# LED_KEY.net
KiCad netlist of a schematic drawn in Altium Designer
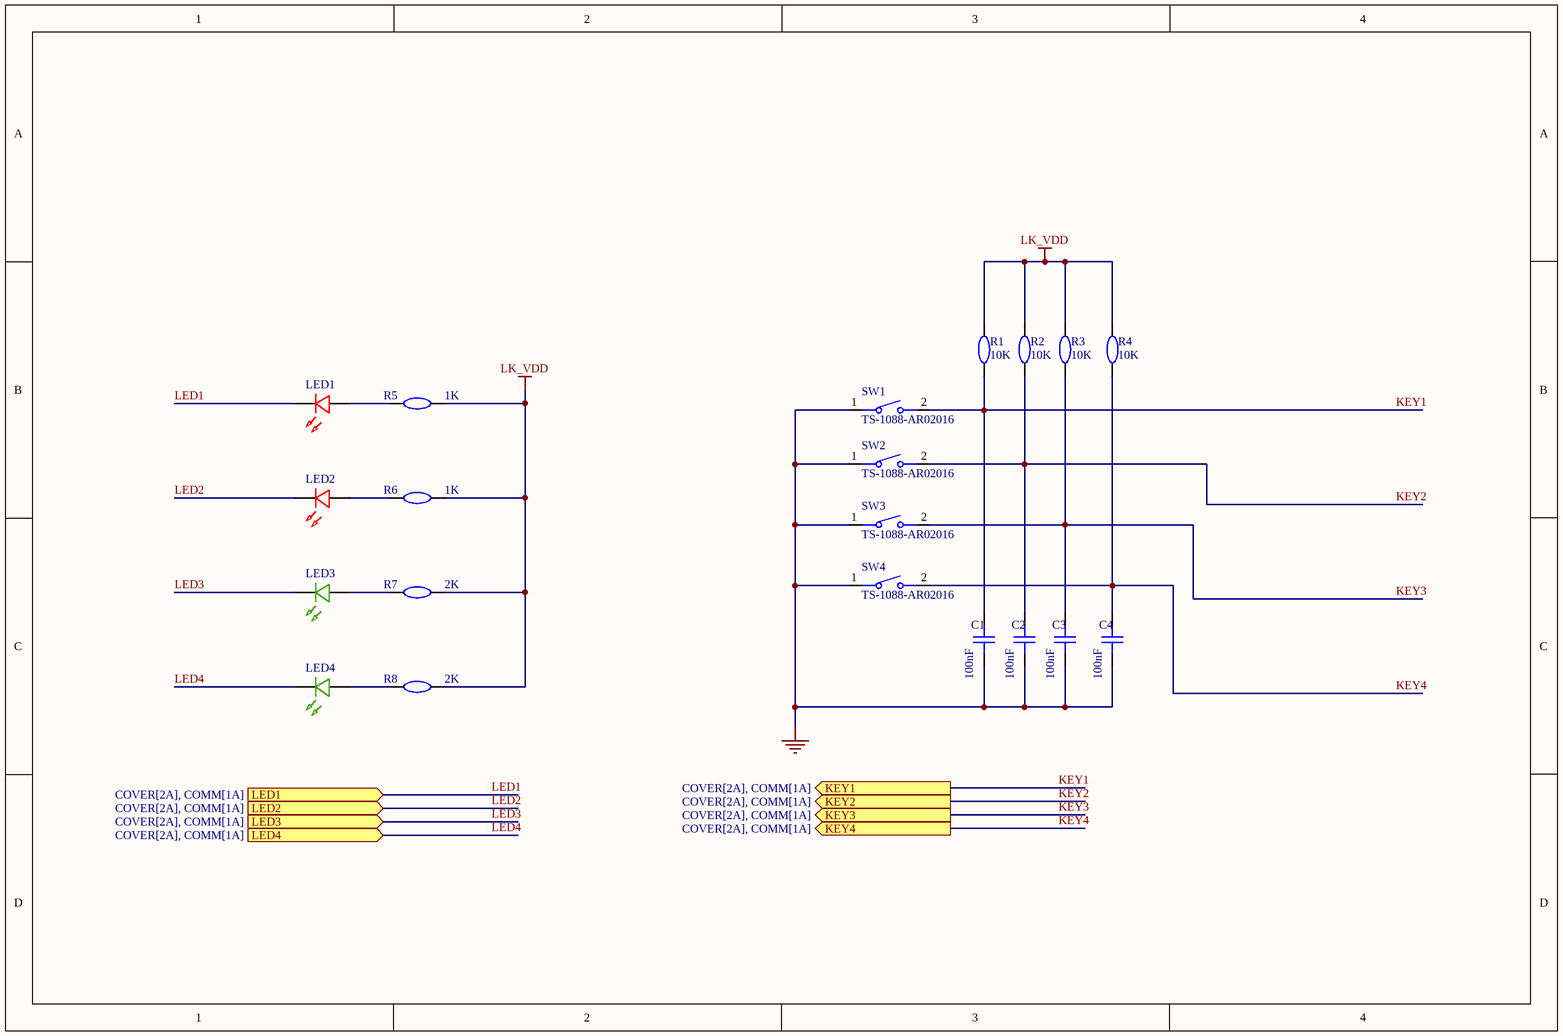
[diagram p0: LED+KEY.SchDoc]

(export (version "E")
  (design (tool "Eeschema 10.0.6"))
  (components
    (comp (ref "C1")
      (value "100nF")
      (footprint "C0402")
      (fields (field (name "NAME") "100nF"))
      (libsource (lib "my_library") (part "CAP_0402"))
    )
    (comp (ref "C2")
      (value "100nF")
      (footprint "C0402")
      (fields (field (name "NAME") "100nF"))
      (libsource (lib "my_library") (part "CAP_0402"))
    )
    (comp (ref "C3")
      (value "100nF")
      (footprint "C0402")
      (fields (field (name "NAME") "100nF"))
      (libsource (lib "my_library") (part "CAP_0402"))
    )
    (comp (ref "C4")
      (value "100nF")
      (footprint "C0402")
      (fields (field (name "NAME") "100nF"))
      (libsource (lib "my_library") (part "CAP_0402"))
    )
    (comp (ref "LED1")
      (value "LED_0603-R")
      (footprint "LED_0603")
      (libsource (lib "my_library") (part "LED_0603-R"))
    )
    (comp (ref "LED2")
      (value "LED_0603-R")
      (footprint "LED_0603")
      (libsource (lib "my_library") (part "LED_0603-R"))
    )
    (comp (ref "LED3")
      (value "LED_0603-R")
      (footprint "LED_0603")
      (libsource (lib "PCB_Project") (part "LED_0603-G"))
    )
    (comp (ref "LED4")
      (value "LED_0603-R")
      (footprint "LED_0603")
      (libsource (lib "PCB_Project") (part "LED_0603-G"))
    )
    (comp (ref "R1")
      (value "10K")
      (footprint "R0402")
      (fields (field (name "NAME") "10K"))
      (libsource (lib "my_library") (part "Res_0402"))
    )
    (comp (ref "R2")
      (value "10K")
      (footprint "R0402")
      (fields (field (name "NAME") "10K"))
      (libsource (lib "my_library") (part "Res_0402"))
    )
    (comp (ref "R3")
      (value "10K")
      (footprint "R0402")
      (fields (field (name "NAME") "10K"))
      (libsource (lib "my_library") (part "Res_0402"))
    )
    (comp (ref "R4")
      (value "10K")
      (footprint "R0402")
      (fields (field (name "NAME") "10K"))
      (libsource (lib "my_library") (part "Res_0402"))
    )
    (comp (ref "R5")
      (value "1K")
      (footprint "R0402")
      (fields (field (name "NAME") "1K"))
      (libsource (lib "my_library") (part "Res_0402"))
    )
    (comp (ref "R6")
      (value "1K")
      (footprint "R0402")
      (fields (field (name "NAME") "1K"))
      (libsource (lib "my_library") (part "Res_0402"))
    )
    (comp (ref "R7")
      (value "2K")
      (footprint "R0402")
      (fields (field (name "NAME") "2K"))
      (libsource (lib "my_library") (part "Res_0402"))
    )
    (comp (ref "R8")
      (value "2K")
      (footprint "R0402")
      (fields (field (name "NAME") "2K"))
      (libsource (lib "my_library") (part "Res_0402"))
    )
    (comp (ref "SW1")
      (value "TS-1088-AR02016")
      (footprint "SW-SMD_L3.9-W3.0-P4.45")
      (fields (field (name "MANUFACTURER") "XUNPU(讯普)") (field (name "NAME") "TS-1088-AR02016"))
      (libsource (lib "my_library") (part "TS-1088-AR02016"))
    )
    (comp (ref "SW2")
      (value "TS-1088-AR02016")
      (footprint "SW-SMD_L3.9-W3.0-P4.45")
      (fields (field (name "MANUFACTURER") "XUNPU(讯普)") (field (name "NAME") "TS-1088-AR02016"))
      (libsource (lib "my_library") (part "TS-1088-AR02016"))
    )
    (comp (ref "SW3")
      (value "TS-1088-AR02016")
      (footprint "SW-SMD_L3.9-W3.0-P4.45")
      (fields (field (name "MANUFACTURER") "XUNPU(讯普)") (field (name "NAME") "TS-1088-AR02016"))
      (libsource (lib "my_library") (part "TS-1088-AR02016"))
    )
    (comp (ref "SW4")
      (value "TS-1088-AR02016")
      (footprint "SW-SMD_L3.9-W3.0-P4.45")
      (fields (field (name "MANUFACTURER") "XUNPU(讯普)") (field (name "NAME") "TS-1088-AR02016"))
      (libsource (lib "my_library") (part "TS-1088-AR02016"))
    )
  )
  (nets
    (net (code "1") (name "/KEY1") (class "Default")
      (node (ref "C1") (pin "2") (pinfunction "2_2") (pintype "passive"))
      (node (ref "R1") (pin "1") (pinfunction "1_1") (pintype "passive"))
      (node (ref "SW1") (pin "2") (pinfunction "2_2") (pintype "passive"))
    )
    (net (code "2") (name "/KEY2") (class "Default")
      (node (ref "C2") (pin "2") (pinfunction "2_2") (pintype "passive"))
      (node (ref "R2") (pin "1") (pinfunction "1_1") (pintype "passive"))
      (node (ref "SW2") (pin "2") (pinfunction "2_2") (pintype "passive"))
    )
    (net (code "3") (name "/KEY3") (class "Default")
      (node (ref "C3") (pin "2") (pinfunction "2_2") (pintype "passive"))
      (node (ref "R3") (pin "1") (pinfunction "1_1") (pintype "passive"))
      (node (ref "SW3") (pin "2") (pinfunction "2_2") (pintype "passive"))
    )
    (net (code "4") (name "/KEY4") (class "Default")
      (node (ref "C4") (pin "2") (pinfunction "2_2") (pintype "passive"))
      (node (ref "R4") (pin "1") (pinfunction "1_1") (pintype "passive"))
      (node (ref "SW4") (pin "2") (pinfunction "2_2") (pintype "passive"))
    )
    (net (code "5") (name "/LED1") (class "Default")
      (node (ref "LED1") (pin "1") (pinfunction "C_1") (pintype "passive"))
    )
    (net (code "6") (name "/LED2") (class "Default")
      (node (ref "LED2") (pin "1") (pinfunction "C_1") (pintype "passive"))
    )
    (net (code "7") (name "/LED3") (class "Default")
      (node (ref "LED3") (pin "1") (pinfunction "C_1") (pintype "passive"))
    )
    (net (code "8") (name "/LED4") (class "Default")
      (node (ref "LED4") (pin "1") (pinfunction "C_1") (pintype "passive"))
    )
    (net (code "9") (name "GND") (class "Default")
      (node (ref "C1") (pin "1") (pinfunction "1_1") (pintype "passive"))
      (node (ref "C2") (pin "1") (pinfunction "1_1") (pintype "passive"))
      (node (ref "C3") (pin "1") (pinfunction "1_1") (pintype "passive"))
      (node (ref "C4") (pin "1") (pinfunction "1_1") (pintype "passive"))
      (node (ref "SW1") (pin "1") (pinfunction "1_1") (pintype "passive"))
      (node (ref "SW2") (pin "1") (pinfunction "1_1") (pintype "passive"))
      (node (ref "SW3") (pin "1") (pinfunction "1_1") (pintype "passive"))
      (node (ref "SW4") (pin "1") (pinfunction "1_1") (pintype "passive"))
    )
    (net (code "10") (name "LK_VDD") (class "Default")
      (node (ref "R1") (pin "2") (pinfunction "2_2") (pintype "passive"))
      (node (ref "R2") (pin "2") (pinfunction "2_2") (pintype "passive"))
      (node (ref "R3") (pin "2") (pinfunction "2_2") (pintype "passive"))
      (node (ref "R4") (pin "2") (pinfunction "2_2") (pintype "passive"))
      (node (ref "R5") (pin "1") (pinfunction "1_1") (pintype "passive"))
      (node (ref "R6") (pin "1") (pinfunction "1_1") (pintype "passive"))
      (node (ref "R7") (pin "1") (pinfunction "1_1") (pintype "passive"))
      (node (ref "R8") (pin "1") (pinfunction "1_1") (pintype "passive"))
    )
    (net (code "11") (name "Net-(LED1-A)") (class "Default")
      (node (ref "LED1") (pin "2") (pinfunction "A_2") (pintype "passive"))
      (node (ref "R5") (pin "2") (pinfunction "2_2") (pintype "passive"))
    )
    (net (code "12") (name "Net-(LED2-A)") (class "Default")
      (node (ref "LED2") (pin "2") (pinfunction "A_2") (pintype "passive"))
      (node (ref "R6") (pin "2") (pinfunction "2_2") (pintype "passive"))
    )
    (net (code "13") (name "Net-(LED3-A)") (class "Default")
      (node (ref "LED3") (pin "2") (pinfunction "A_2") (pintype "passive"))
      (node (ref "R7") (pin "2") (pinfunction "2_2") (pintype "passive"))
    )
    (net (code "14") (name "Net-(LED4-A)") (class "Default")
      (node (ref "LED4") (pin "2") (pinfunction "A_2") (pintype "passive"))
      (node (ref "R8") (pin "2") (pinfunction "2_2") (pintype "passive"))
    )
  )
)
